# LDConnector_v3.net
KiCad netlist of a schematic drawn in EAGLE
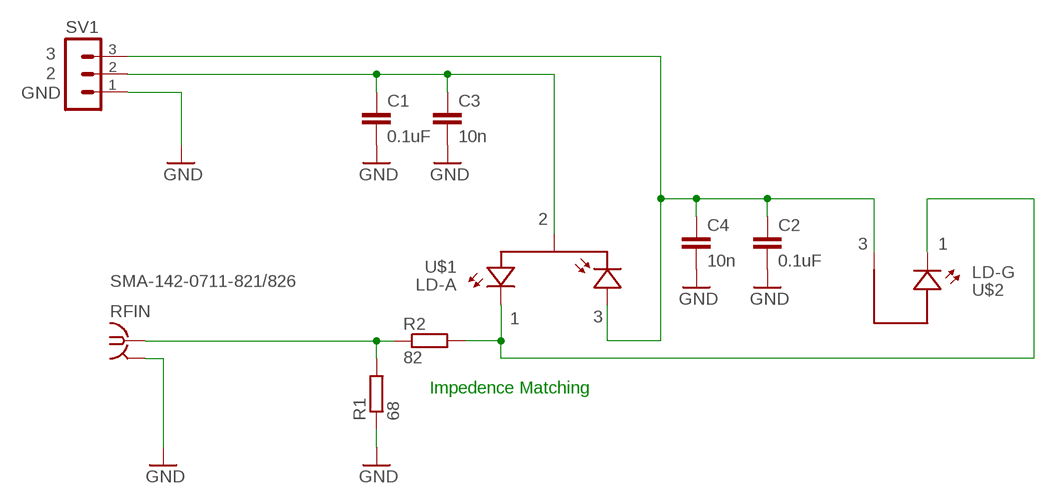
[diagram p0: schematic, sheet 1]

(export (version "E")
  (design (tool "Eeschema 10.0.6"))
  (components
    (comp (ref "C1")
      (value "0.1uF")
      (footprint "eagle-import:C0603")
      (libsource (lib "eagle-import") (part "C-EUC0603"))
    )
    (comp (ref "C2")
      (value "0.1uF")
      (footprint "eagle-import:C0603")
      (libsource (lib "eagle-import") (part "C-EUC0603"))
    )
    (comp (ref "C3")
      (value "10n")
      (footprint "eagle-import:C0603")
      (libsource (lib "eagle-import") (part "C-EUC0603"))
    )
    (comp (ref "C4")
      (value "10n")
      (footprint "eagle-import:C0603")
      (libsource (lib "eagle-import") (part "C-EUC0603"))
    )
    (comp (ref "R1")
      (value "68")
      (footprint "eagle-import:R0603")
      (libsource (lib "eagle-import") (part "R-EU_R0603"))
    )
    (comp (ref "R2")
      (value "82")
      (footprint "eagle-import:R0603")
      (libsource (lib "eagle-import") (part "R-EU_R0603"))
    )
    (comp (ref "RFIN")
      (value "SMA-142-0711-821/826")
      (footprint "eagle-import:J502-ND-142-0711-821_826")
      (fields (field (name "MF") "JOHNSON COMPONENTS") (field (name "MPN") "142-0711-821"))
      (libsource (lib "eagle-import") (part "SMA-142-0711-821/826"))
    )
    (comp (ref "SV1")
      (value "MA03-1")
      (footprint "eagle-import:MA03-1")
      (libsource (lib "eagle-import") (part "MA03-1"))
    )
    (comp (ref "U$1")
      (value "LD-A")
      (footprint "eagle-import:TYPEA")
      (libsource (lib "eagle-import") (part "LD-A"))
    )
    (comp (ref "U$2")
      (value "LD-G")
      (footprint "eagle-import:TYPEG")
      (libsource (lib "eagle-import") (part "LD-G"))
    )
  )
  (nets
    (net (code "1") (name "GND") (class "Default")
      (node (ref "C1") (pin "2") (pinfunction "2_2") (pintype "passive"))
      (node (ref "C2") (pin "2") (pinfunction "2_2") (pintype "passive"))
      (node (ref "C3") (pin "2") (pinfunction "2_2") (pintype "passive"))
      (node (ref "C4") (pin "2") (pinfunction "2_2") (pintype "passive"))
      (node (ref "R1") (pin "1") (pinfunction "1_1") (pintype "passive"))
      (node (ref "RFIN") (pin "G@1") (pinfunction "2_G@1") (pintype "passive"))
      (node (ref "RFIN") (pin "G@2") (pinfunction "2_G@2") (pintype "passive"))
      (node (ref "RFIN") (pin "G@3") (pinfunction "2_G@3") (pintype "passive"))
      (node (ref "RFIN") (pin "G@4") (pinfunction "2_G@4") (pintype "passive"))
      (node (ref "SV1") (pin "1") (pinfunction "1_1") (pintype "passive"))
    )
    (net (code "2") (name "Net-(R1-Pad2)") (class "Default")
      (node (ref "R1") (pin "2") (pinfunction "2_2") (pintype "passive"))
      (node (ref "R2") (pin "1") (pinfunction "1_1") (pintype "passive"))
      (node (ref "RFIN") (pin "1") (pinfunction "1_1") (pintype "passive"))
    )
    (net (code "3") (name "Net-(U$1-LDA-PDC)") (class "Default")
      (node (ref "C1") (pin "1") (pinfunction "1_1") (pintype "passive"))
      (node (ref "C3") (pin "1") (pinfunction "1_1") (pintype "passive"))
      (node (ref "SV1") (pin "2") (pinfunction "2_2") (pintype "passive"))
      (node (ref "U$1") (pin "2-PDC-LDA") (pinfunction "LDA-PDC_2-PDC-LDA") (pintype "passive"))
    )
    (net (code "4") (name "Net-(U$1-LDC)") (class "Default")
      (node (ref "R2") (pin "2") (pinfunction "2_2") (pintype "passive"))
      (node (ref "U$1") (pin "1-LDC") (pinfunction "LDC_1-LDC") (pintype "passive"))
      (node (ref "U$2") (pin "1-LDC") (pinfunction "LDC_1-LDC") (pintype "passive"))
    )
    (net (code "5") (name "Net-(U$1-PDA)") (class "Default")
      (node (ref "C2") (pin "1") (pinfunction "1_1") (pintype "passive"))
      (node (ref "C4") (pin "1") (pinfunction "1_1") (pintype "passive"))
      (node (ref "SV1") (pin "3") (pinfunction "3_3") (pintype "passive"))
      (node (ref "U$1") (pin "3-PDA") (pinfunction "PDA_3-PDA") (pintype "passive"))
      (node (ref "U$2") (pin "3-LDA") (pinfunction "LDA_3-LDA") (pintype "passive"))
    )
  )
)
